# untitled.net
KiCad netlist of a schematic drawn in EAGLE
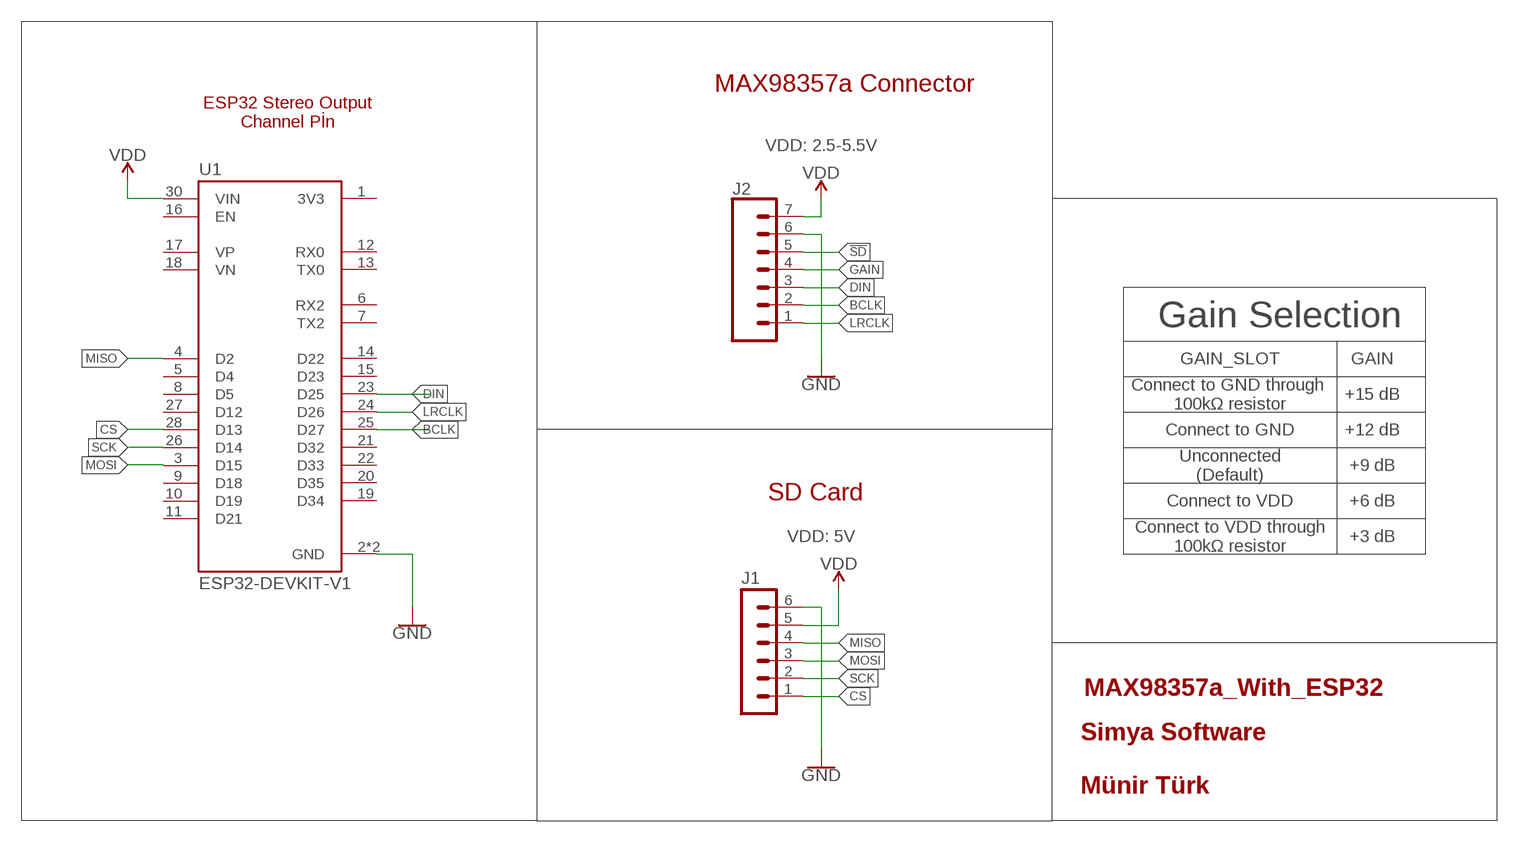
[diagram p0: schematic, sheet 1]

(export (version "E")
  (design (tool "Eeschema 10.0.6"))
  (components
    (comp (ref "J1")
      (value "MA06-1")
      (footprint "eagle-import:MA06-1")
      (libsource (lib "eagle-import") (part "MA06-1"))
    )
    (comp (ref "J2")
      (value "CONN_07NO_SILK")
      (footprint "eagle-import:1X07_NO_SILK")
      (libsource (lib "eagle-import") (part "CONN_07NO_SILK"))
    )
    (comp (ref "U1")
      (value "ESP32-DEVKIT-V1")
      (footprint "eagle-import:MODULE_ESP32_DEVKIT_V1")
      (fields (field (name "MF") "Do it"))
      (libsource (lib "eagle-import") (part "ESP32-DEVKIT-V1"))
    )
  )
  (nets
    (net (code "1") (name "/~{SD}") (class "Default")
      (node (ref "J2") (pin "5") (pinfunction "5_5") (pintype "passive"))
    )
    (net (code "2") (name "BCLK") (class "Default")
      (node (ref "J2") (pin "2") (pinfunction "2_2") (pintype "passive"))
      (node (ref "U1") (pin "25") (pinfunction "D27_25") (pintype "bidirectional"))
    )
    (net (code "3") (name "CS") (class "Default")
      (node (ref "J1") (pin "1") (pinfunction "1_1") (pintype "passive"))
      (node (ref "U1") (pin "28") (pinfunction "D13_28") (pintype "bidirectional"))
    )
    (net (code "4") (name "DIN") (class "Default")
      (node (ref "J2") (pin "3") (pinfunction "3_3") (pintype "passive"))
      (node (ref "U1") (pin "23") (pinfunction "D25_23") (pintype "bidirectional"))
    )
    (net (code "5") (name "GAIN") (class "Default")
      (node (ref "J2") (pin "4") (pinfunction "4_4") (pintype "passive"))
    )
    (net (code "6") (name "GND") (class "Default")
      (node (ref "J1") (pin "6") (pinfunction "6_6") (pintype "passive"))
      (node (ref "J2") (pin "6") (pinfunction "6_6") (pintype "passive"))
      (node (ref "U1") (pin "2") (pinfunction "GND_2") (pintype "power_in"))
      (node (ref "U1") (pin "29") (pinfunction "GND_29") (pintype "power_in"))
    )
    (net (code "7") (name "LRCLK") (class "Default")
      (node (ref "J2") (pin "1") (pinfunction "1_1") (pintype "passive"))
      (node (ref "U1") (pin "24") (pinfunction "D26_24") (pintype "bidirectional"))
    )
    (net (code "8") (name "MISO") (class "Default")
      (node (ref "J1") (pin "4") (pinfunction "4_4") (pintype "passive"))
      (node (ref "U1") (pin "4") (pinfunction "D2_4") (pintype "bidirectional"))
    )
    (net (code "9") (name "MOSI") (class "Default")
      (node (ref "J1") (pin "3") (pinfunction "3_3") (pintype "passive"))
      (node (ref "U1") (pin "3") (pinfunction "D15_3") (pintype "bidirectional"))
    )
    (net (code "10") (name "SCK") (class "Default")
      (node (ref "J1") (pin "2") (pinfunction "2_2") (pintype "passive"))
      (node (ref "U1") (pin "26") (pinfunction "D14_26") (pintype "bidirectional"))
    )
    (net (code "11") (name "VDD") (class "Default")
      (node (ref "J1") (pin "5") (pinfunction "5_5") (pintype "passive"))
      (node (ref "J2") (pin "7") (pinfunction "7_7") (pintype "passive"))
      (node (ref "U1") (pin "30") (pinfunction "VIN_30") (pintype "input"))
    )
    (net (code "12") (name "unconnected-(U1-3V3-Pad1)") (class "Default")
      (node (ref "U1") (pin "1") (pinfunction "3V3_1") (pintype "output"))
    )
    (net (code "13") (name "unconnected-(U1-D4-Pad5)") (class "Default")
      (node (ref "U1") (pin "5") (pinfunction "D4_5") (pintype "bidirectional"))
    )
    (net (code "14") (name "unconnected-(U1-D5-Pad8)") (class "Default")
      (node (ref "U1") (pin "8") (pinfunction "D5_8") (pintype "bidirectional"))
    )
    (net (code "15") (name "unconnected-(U1-D12-Pad27)") (class "Default")
      (node (ref "U1") (pin "27") (pinfunction "D12_27") (pintype "bidirectional"))
    )
    (net (code "16") (name "unconnected-(U1-D18-Pad9)") (class "Default")
      (node (ref "U1") (pin "9") (pinfunction "D18_9") (pintype "bidirectional"))
    )
    (net (code "17") (name "unconnected-(U1-D19-Pad10)") (class "Default")
      (node (ref "U1") (pin "10") (pinfunction "D19_10") (pintype "bidirectional"))
    )
    (net (code "18") (name "unconnected-(U1-D21-Pad11)") (class "Default")
      (node (ref "U1") (pin "11") (pinfunction "D21_11") (pintype "bidirectional"))
    )
    (net (code "19") (name "unconnected-(U1-D22-Pad14)") (class "Default")
      (node (ref "U1") (pin "14") (pinfunction "D22_14") (pintype "bidirectional"))
    )
    (net (code "20") (name "unconnected-(U1-D23-Pad15)") (class "Default")
      (node (ref "U1") (pin "15") (pinfunction "D23_15") (pintype "bidirectional"))
    )
    (net (code "21") (name "unconnected-(U1-D32-Pad21)") (class "Default")
      (node (ref "U1") (pin "21") (pinfunction "D32_21") (pintype "bidirectional"))
    )
    (net (code "22") (name "unconnected-(U1-D33-Pad22)") (class "Default")
      (node (ref "U1") (pin "22") (pinfunction "D33_22") (pintype "bidirectional"))
    )
    (net (code "23") (name "unconnected-(U1-D34-Pad19)") (class "Default")
      (node (ref "U1") (pin "19") (pinfunction "D34_19") (pintype "bidirectional"))
    )
    (net (code "24") (name "unconnected-(U1-D35-Pad20)") (class "Default")
      (node (ref "U1") (pin "20") (pinfunction "D35_20") (pintype "bidirectional"))
    )
    (net (code "25") (name "unconnected-(U1-EN-Pad16)") (class "Default")
      (node (ref "U1") (pin "16") (pinfunction "EN_16") (pintype "input"))
    )
    (net (code "26") (name "unconnected-(U1-RX0-Pad12)") (class "Default")
      (node (ref "U1") (pin "12") (pinfunction "RX0_12") (pintype "input"))
    )
    (net (code "27") (name "unconnected-(U1-RX2-Pad6)") (class "Default")
      (node (ref "U1") (pin "6") (pinfunction "RX2_6") (pintype "input"))
    )
    (net (code "28") (name "unconnected-(U1-TX0-Pad13)") (class "Default")
      (node (ref "U1") (pin "13") (pinfunction "TX0_13") (pintype "output"))
    )
    (net (code "29") (name "unconnected-(U1-TX2-Pad7)") (class "Default")
      (node (ref "U1") (pin "7") (pinfunction "TX2_7") (pintype "output"))
    )
    (net (code "30") (name "unconnected-(U1-VN-Pad18)") (class "Default")
      (node (ref "U1") (pin "18") (pinfunction "VN_18") (pintype "bidirectional"))
    )
    (net (code "31") (name "unconnected-(U1-VP-Pad17)") (class "Default")
      (node (ref "U1") (pin "17") (pinfunction "VP_17") (pintype "bidirectional"))
    )
  )
)
